# ESP32_VERSION_2.net
KiCad netlist of a schematic drawn in EAGLE
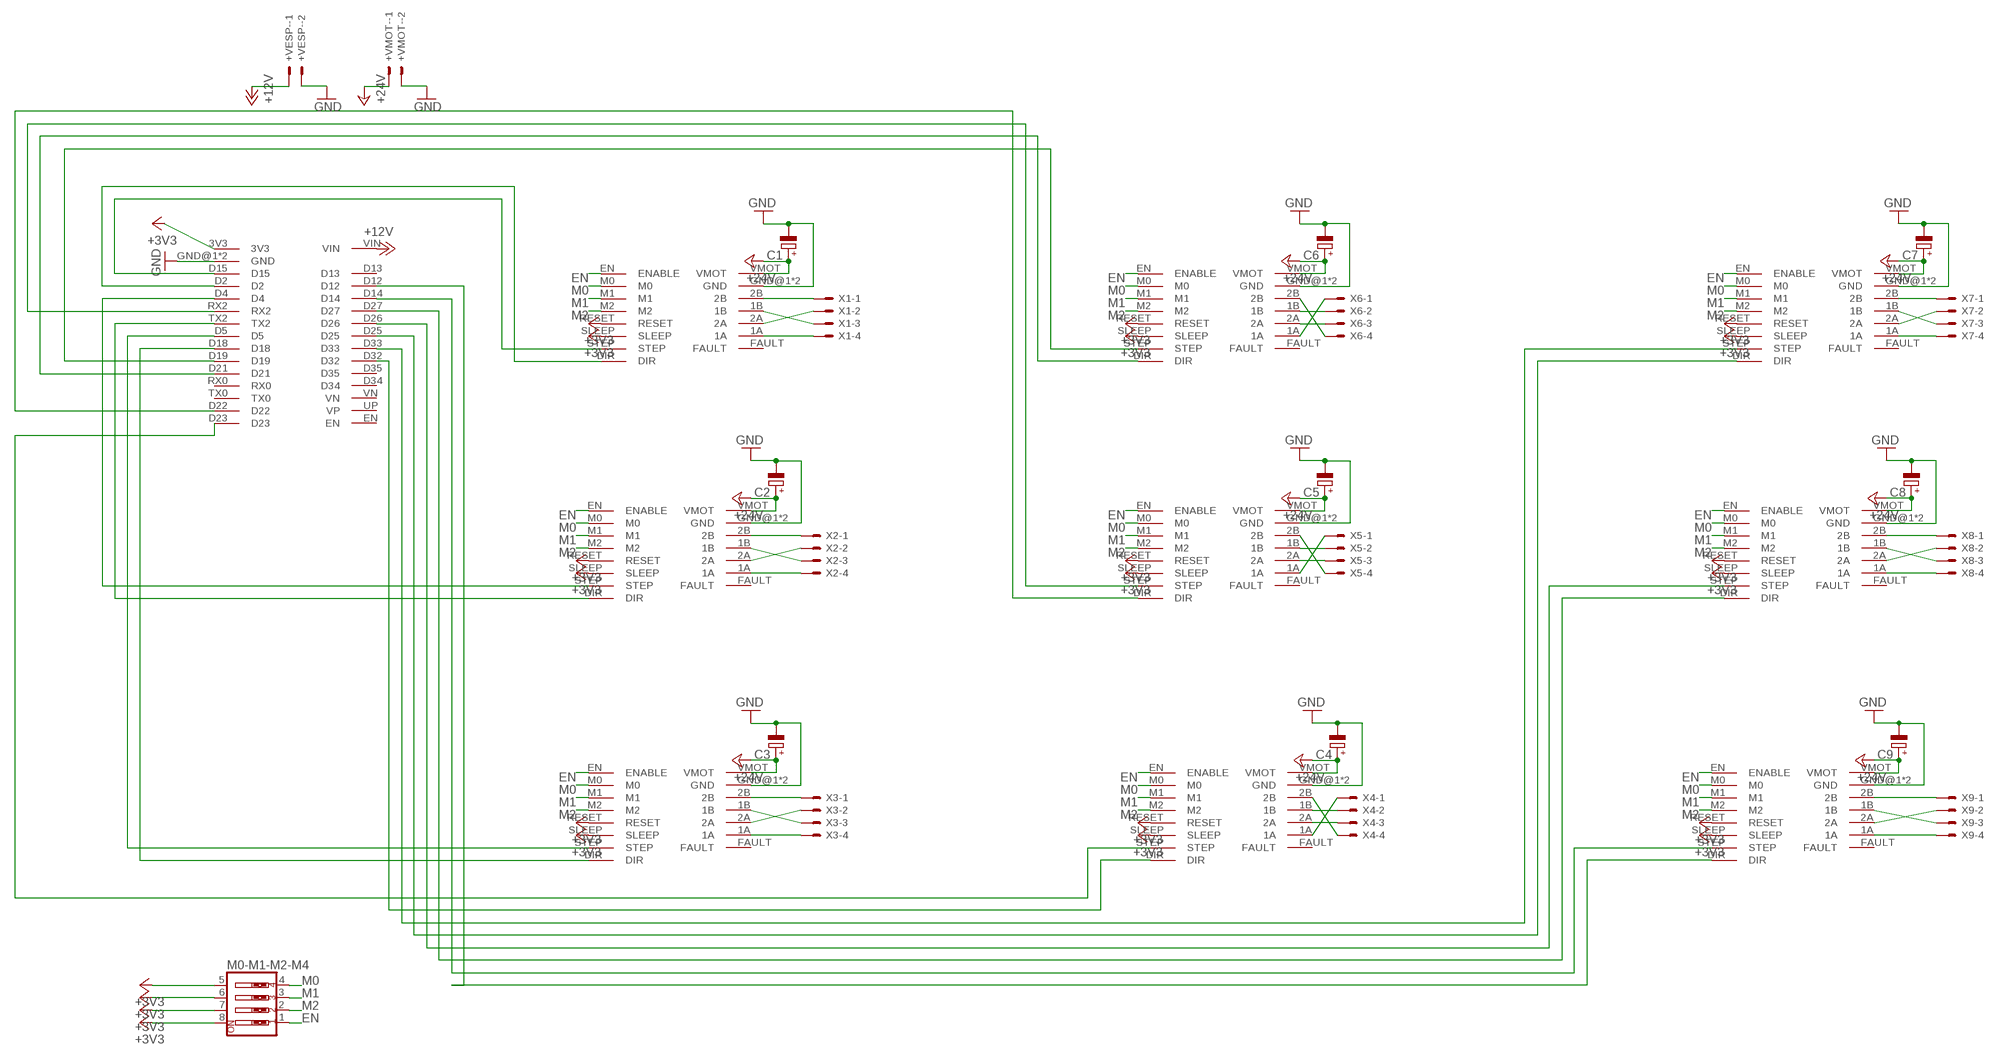
[diagram p0: schematic, sheet 1]

(export (version "E")
  (design (tool "Eeschema 10.0.6"))
  (components
    (comp (ref "+VESP-")
      (value "22-23-2021")
      (footprint "eagle-import:22-23-2021")
      (fields (field (name "MF") "MOLEX"))
      (libsource (lib "eagle-import") (part "22-23-2021"))
    )
    (comp (ref "+VMOT-")
      (value "22-23-2021")
      (footprint "eagle-import:22-23-2021")
      (fields (field (name "MF") "MOLEX"))
      (libsource (lib "eagle-import") (part "22-23-2021"))
    )
    (comp (ref "C1")
      (value "CPOL-EUE3.5-8")
      (footprint "eagle-import:E3,5-8")
      (libsource (lib "eagle-import") (part "CPOL-EUE3.5-8"))
    )
    (comp (ref "C2")
      (value "CPOL-EUE3.5-8")
      (footprint "eagle-import:E3,5-8")
      (libsource (lib "eagle-import") (part "CPOL-EUE3.5-8"))
    )
    (comp (ref "C3")
      (value "CPOL-EUE3.5-8")
      (footprint "eagle-import:E3,5-8")
      (libsource (lib "eagle-import") (part "CPOL-EUE3.5-8"))
    )
    (comp (ref "C4")
      (value "CPOL-EUE3.5-8")
      (footprint "eagle-import:E3,5-8")
      (libsource (lib "eagle-import") (part "CPOL-EUE3.5-8"))
    )
    (comp (ref "C5")
      (value "CPOL-EUE3.5-8")
      (footprint "eagle-import:E3,5-8")
      (libsource (lib "eagle-import") (part "CPOL-EUE3.5-8"))
    )
    (comp (ref "C6")
      (value "CPOL-EUE3.5-8")
      (footprint "eagle-import:E3,5-8")
      (libsource (lib "eagle-import") (part "CPOL-EUE3.5-8"))
    )
    (comp (ref "C7")
      (value "CPOL-EUE3.5-8")
      (footprint "eagle-import:E3,5-8")
      (libsource (lib "eagle-import") (part "CPOL-EUE3.5-8"))
    )
    (comp (ref "C8")
      (value "CPOL-EUE3.5-8")
      (footprint "eagle-import:E3,5-8")
      (libsource (lib "eagle-import") (part "CPOL-EUE3.5-8"))
    )
    (comp (ref "C9")
      (value "CPOL-EUE3.5-8")
      (footprint "eagle-import:E3,5-8")
      (libsource (lib "eagle-import") (part "CPOL-EUE3.5-8"))
    )
    (comp (ref "M0-M1-M2-M4")
      (value "SW_DIP-4")
      (footprint "eagle-import:EDG-04")
      (libsource (lib "eagle-import") (part "SW_DIP-4"))
    )
    (comp (ref "U$1")
      (value "DRV8825")
      (footprint "eagle-import:DRV8825")
      (libsource (lib "eagle-import") (part "DRV8825"))
    )
    (comp (ref "U$2")
      (value "DRV8825")
      (footprint "eagle-import:DRV8825")
      (libsource (lib "eagle-import") (part "DRV8825"))
    )
    (comp (ref "U$3")
      (value "STEPPER 0")
      (footprint "eagle-import:DRV8825")
      (libsource (lib "eagle-import") (part "DRV8825"))
    )
    (comp (ref "U$4")
      (value "DRV8825")
      (footprint "eagle-import:DRV8825")
      (libsource (lib "eagle-import") (part "DRV8825"))
    )
    (comp (ref "U$5")
      (value "DRV8825")
      (footprint "eagle-import:DRV8825")
      (libsource (lib "eagle-import") (part "DRV8825"))
    )
    (comp (ref "U$6")
      (value "DRV8825")
      (footprint "eagle-import:DRV8825")
      (libsource (lib "eagle-import") (part "DRV8825"))
    )
    (comp (ref "U$7")
      (value "DRV8825")
      (footprint "eagle-import:DRV8825")
      (libsource (lib "eagle-import") (part "DRV8825"))
    )
    (comp (ref "U$8")
      (value "DRV8825")
      (footprint "eagle-import:DRV8825")
      (libsource (lib "eagle-import") (part "DRV8825"))
    )
    (comp (ref "U$9")
      (value "DRV8825")
      (footprint "eagle-import:DRV8825")
      (libsource (lib "eagle-import") (part "DRV8825"))
    )
    (comp (ref "U$10")
      (value "ESP32")
      (footprint "eagle-import:ESP32")
      (libsource (lib "eagle-import") (part "ESP32"))
    )
    (comp (ref "X1")
      (value "22-23-2041")
      (footprint "eagle-import:22-23-2041")
      (fields (field (name "MF") "MOLEX"))
      (libsource (lib "eagle-import") (part "22-23-2041"))
    )
    (comp (ref "X2")
      (value "22-23-2041")
      (footprint "eagle-import:22-23-2041")
      (fields (field (name "MF") "MOLEX"))
      (libsource (lib "eagle-import") (part "22-23-2041"))
    )
    (comp (ref "X3")
      (value "22-23-2041")
      (footprint "eagle-import:22-23-2041")
      (fields (field (name "MF") "MOLEX"))
      (libsource (lib "eagle-import") (part "22-23-2041"))
    )
    (comp (ref "X4")
      (value "22-23-2041")
      (footprint "eagle-import:22-23-2041")
      (fields (field (name "MF") "MOLEX"))
      (libsource (lib "eagle-import") (part "22-23-2041"))
    )
    (comp (ref "X5")
      (value "22-23-2041")
      (footprint "eagle-import:22-23-2041")
      (fields (field (name "MF") "MOLEX"))
      (libsource (lib "eagle-import") (part "22-23-2041"))
    )
    (comp (ref "X6")
      (value "22-23-2041")
      (footprint "eagle-import:22-23-2041")
      (fields (field (name "MF") "MOLEX"))
      (libsource (lib "eagle-import") (part "22-23-2041"))
    )
    (comp (ref "X7")
      (value "22-23-2041")
      (footprint "eagle-import:22-23-2041")
      (fields (field (name "MF") "MOLEX"))
      (libsource (lib "eagle-import") (part "22-23-2041"))
    )
    (comp (ref "X8")
      (value "22-23-2041")
      (footprint "eagle-import:22-23-2041")
      (fields (field (name "MF") "MOLEX"))
      (libsource (lib "eagle-import") (part "22-23-2041"))
    )
    (comp (ref "X9")
      (value "22-23-2041")
      (footprint "eagle-import:22-23-2041")
      (fields (field (name "MF") "MOLEX"))
      (libsource (lib "eagle-import") (part "22-23-2041"))
    )
  )
  (nets
    (net (code "1") (name "+3V3") (class "Default")
      (node (ref "M0-M1-M2-M4") (pin "5") (pinfunction "5_5") (pintype "passive"))
      (node (ref "M0-M1-M2-M4") (pin "6") (pinfunction "6_6") (pintype "passive"))
      (node (ref "M0-M1-M2-M4") (pin "7") (pinfunction "7_7") (pintype "passive"))
      (node (ref "M0-M1-M2-M4") (pin "8") (pinfunction "8_8") (pintype "passive"))
      (node (ref "U$1") (pin "RESET") (pinfunction "RESET_RESET") (pintype "bidirectional"))
      (node (ref "U$1") (pin "SLEEP") (pinfunction "SLEEP_SLEEP") (pintype "bidirectional"))
      (node (ref "U$10") (pin "3V3") (pinfunction "3V3_3V3") (pintype "bidirectional"))
      (node (ref "U$2") (pin "RESET") (pinfunction "RESET_RESET") (pintype "bidirectional"))
      (node (ref "U$2") (pin "SLEEP") (pinfunction "SLEEP_SLEEP") (pintype "bidirectional"))
      (node (ref "U$3") (pin "RESET") (pinfunction "RESET_RESET") (pintype "bidirectional"))
      (node (ref "U$3") (pin "SLEEP") (pinfunction "SLEEP_SLEEP") (pintype "bidirectional"))
      (node (ref "U$4") (pin "RESET") (pinfunction "RESET_RESET") (pintype "bidirectional"))
      (node (ref "U$4") (pin "SLEEP") (pinfunction "SLEEP_SLEEP") (pintype "bidirectional"))
      (node (ref "U$5") (pin "RESET") (pinfunction "RESET_RESET") (pintype "bidirectional"))
      (node (ref "U$5") (pin "SLEEP") (pinfunction "SLEEP_SLEEP") (pintype "bidirectional"))
      (node (ref "U$6") (pin "RESET") (pinfunction "RESET_RESET") (pintype "bidirectional"))
      (node (ref "U$6") (pin "SLEEP") (pinfunction "SLEEP_SLEEP") (pintype "bidirectional"))
      (node (ref "U$7") (pin "RESET") (pinfunction "RESET_RESET") (pintype "bidirectional"))
      (node (ref "U$7") (pin "SLEEP") (pinfunction "SLEEP_SLEEP") (pintype "bidirectional"))
      (node (ref "U$8") (pin "RESET") (pinfunction "RESET_RESET") (pintype "bidirectional"))
      (node (ref "U$8") (pin "SLEEP") (pinfunction "SLEEP_SLEEP") (pintype "bidirectional"))
      (node (ref "U$9") (pin "RESET") (pinfunction "RESET_RESET") (pintype "bidirectional"))
      (node (ref "U$9") (pin "SLEEP") (pinfunction "SLEEP_SLEEP") (pintype "bidirectional"))
    )
    (net (code "2") (name "+12V") (class "Default")
      (node (ref "+VESP-") (pin "1") (pinfunction "S_1") (pintype "passive"))
      (node (ref "U$10") (pin "VIN") (pinfunction "VIN_VIN") (pintype "bidirectional"))
    )
    (net (code "3") (name "+24V") (class "Default")
      (node (ref "+VMOT-") (pin "1") (pinfunction "S_1") (pintype "passive"))
      (node (ref "C1") (pin "+") (pinfunction "+_+") (pintype "passive"))
      (node (ref "C2") (pin "+") (pinfunction "+_+") (pintype "passive"))
      (node (ref "C3") (pin "+") (pinfunction "+_+") (pintype "passive"))
      (node (ref "C4") (pin "+") (pinfunction "+_+") (pintype "passive"))
      (node (ref "C5") (pin "+") (pinfunction "+_+") (pintype "passive"))
      (node (ref "C6") (pin "+") (pinfunction "+_+") (pintype "passive"))
      (node (ref "C7") (pin "+") (pinfunction "+_+") (pintype "passive"))
      (node (ref "C8") (pin "+") (pinfunction "+_+") (pintype "passive"))
      (node (ref "C9") (pin "+") (pinfunction "+_+") (pintype "passive"))
      (node (ref "U$1") (pin "VMOT") (pinfunction "VMOT_VMOT") (pintype "bidirectional"))
      (node (ref "U$2") (pin "VMOT") (pinfunction "VMOT_VMOT") (pintype "bidirectional"))
      (node (ref "U$3") (pin "VMOT") (pinfunction "VMOT_VMOT") (pintype "bidirectional"))
      (node (ref "U$4") (pin "VMOT") (pinfunction "VMOT_VMOT") (pintype "bidirectional"))
      (node (ref "U$5") (pin "VMOT") (pinfunction "VMOT_VMOT") (pintype "bidirectional"))
      (node (ref "U$6") (pin "VMOT") (pinfunction "VMOT_VMOT") (pintype "bidirectional"))
      (node (ref "U$7") (pin "VMOT") (pinfunction "VMOT_VMOT") (pintype "bidirectional"))
      (node (ref "U$8") (pin "VMOT") (pinfunction "VMOT_VMOT") (pintype "bidirectional"))
      (node (ref "U$9") (pin "VMOT") (pinfunction "VMOT_VMOT") (pintype "bidirectional"))
    )
    (net (code "4") (name "/EN") (class "Default")
      (node (ref "M0-M1-M2-M4") (pin "1") (pinfunction "1_1") (pintype "passive"))
      (node (ref "U$1") (pin "EN") (pinfunction "ENABLE_EN") (pintype "bidirectional"))
      (node (ref "U$2") (pin "EN") (pinfunction "ENABLE_EN") (pintype "bidirectional"))
      (node (ref "U$3") (pin "EN") (pinfunction "ENABLE_EN") (pintype "bidirectional"))
      (node (ref "U$4") (pin "EN") (pinfunction "ENABLE_EN") (pintype "bidirectional"))
      (node (ref "U$5") (pin "EN") (pinfunction "ENABLE_EN") (pintype "bidirectional"))
      (node (ref "U$6") (pin "EN") (pinfunction "ENABLE_EN") (pintype "bidirectional"))
      (node (ref "U$7") (pin "EN") (pinfunction "ENABLE_EN") (pintype "bidirectional"))
      (node (ref "U$8") (pin "EN") (pinfunction "ENABLE_EN") (pintype "bidirectional"))
      (node (ref "U$9") (pin "EN") (pinfunction "ENABLE_EN") (pintype "bidirectional"))
    )
    (net (code "5") (name "/M0") (class "Default")
      (node (ref "M0-M1-M2-M4") (pin "4") (pinfunction "4_4") (pintype "passive"))
      (node (ref "U$1") (pin "M0") (pinfunction "M0_M0") (pintype "bidirectional"))
      (node (ref "U$2") (pin "M0") (pinfunction "M0_M0") (pintype "bidirectional"))
      (node (ref "U$3") (pin "M0") (pinfunction "M0_M0") (pintype "bidirectional"))
      (node (ref "U$4") (pin "M0") (pinfunction "M0_M0") (pintype "bidirectional"))
      (node (ref "U$5") (pin "M0") (pinfunction "M0_M0") (pintype "bidirectional"))
      (node (ref "U$6") (pin "M0") (pinfunction "M0_M0") (pintype "bidirectional"))
      (node (ref "U$7") (pin "M0") (pinfunction "M0_M0") (pintype "bidirectional"))
      (node (ref "U$8") (pin "M0") (pinfunction "M0_M0") (pintype "bidirectional"))
      (node (ref "U$9") (pin "M0") (pinfunction "M0_M0") (pintype "bidirectional"))
    )
    (net (code "6") (name "/M1") (class "Default")
      (node (ref "M0-M1-M2-M4") (pin "3") (pinfunction "3_3") (pintype "passive"))
      (node (ref "U$1") (pin "M1") (pinfunction "M1_M1") (pintype "bidirectional"))
      (node (ref "U$2") (pin "M1") (pinfunction "M1_M1") (pintype "bidirectional"))
      (node (ref "U$3") (pin "M1") (pinfunction "M1_M1") (pintype "bidirectional"))
      (node (ref "U$4") (pin "M1") (pinfunction "M1_M1") (pintype "bidirectional"))
      (node (ref "U$5") (pin "M1") (pinfunction "M1_M1") (pintype "bidirectional"))
      (node (ref "U$6") (pin "M1") (pinfunction "M1_M1") (pintype "bidirectional"))
      (node (ref "U$7") (pin "M1") (pinfunction "M1_M1") (pintype "bidirectional"))
      (node (ref "U$8") (pin "M1") (pinfunction "M1_M1") (pintype "bidirectional"))
      (node (ref "U$9") (pin "M1") (pinfunction "M1_M1") (pintype "bidirectional"))
    )
    (net (code "7") (name "/M2") (class "Default")
      (node (ref "M0-M1-M2-M4") (pin "2") (pinfunction "2_2") (pintype "passive"))
      (node (ref "U$1") (pin "M2") (pinfunction "M2_M2") (pintype "bidirectional"))
      (node (ref "U$2") (pin "M2") (pinfunction "M2_M2") (pintype "bidirectional"))
      (node (ref "U$3") (pin "M2") (pinfunction "M2_M2") (pintype "bidirectional"))
      (node (ref "U$4") (pin "M2") (pinfunction "M2_M2") (pintype "bidirectional"))
      (node (ref "U$5") (pin "M2") (pinfunction "M2_M2") (pintype "bidirectional"))
      (node (ref "U$6") (pin "M2") (pinfunction "M2_M2") (pintype "bidirectional"))
      (node (ref "U$7") (pin "M2") (pinfunction "M2_M2") (pintype "bidirectional"))
      (node (ref "U$8") (pin "M2") (pinfunction "M2_M2") (pintype "bidirectional"))
      (node (ref "U$9") (pin "M2") (pinfunction "M2_M2") (pintype "bidirectional"))
    )
    (net (code "8") (name "GND") (class "Default")
      (node (ref "+VESP-") (pin "2") (pinfunction "S_2") (pintype "passive"))
      (node (ref "+VMOT-") (pin "2") (pinfunction "S_2") (pintype "passive"))
      (node (ref "C1") (pin "-") (pinfunction "-_-") (pintype "passive"))
      (node (ref "C2") (pin "-") (pinfunction "-_-") (pintype "passive"))
      (node (ref "C3") (pin "-") (pinfunction "-_-") (pintype "passive"))
      (node (ref "C4") (pin "-") (pinfunction "-_-") (pintype "passive"))
      (node (ref "C5") (pin "-") (pinfunction "-_-") (pintype "passive"))
      (node (ref "C6") (pin "-") (pinfunction "-_-") (pintype "passive"))
      (node (ref "C7") (pin "-") (pinfunction "-_-") (pintype "passive"))
      (node (ref "C8") (pin "-") (pinfunction "-_-") (pintype "passive"))
      (node (ref "C9") (pin "-") (pinfunction "-_-") (pintype "passive"))
      (node (ref "U$1") (pin "GND@1") (pinfunction "GND_GND@1") (pintype "bidirectional"))
      (node (ref "U$1") (pin "GND@2") (pinfunction "GND_GND@2") (pintype "bidirectional"))
      (node (ref "U$10") (pin "GND@1") (pinfunction "GND_GND@1") (pintype "bidirectional"))
      (node (ref "U$10") (pin "GND@2") (pinfunction "GND_GND@2") (pintype "bidirectional"))
      (node (ref "U$2") (pin "GND@1") (pinfunction "GND_GND@1") (pintype "bidirectional"))
      (node (ref "U$2") (pin "GND@2") (pinfunction "GND_GND@2") (pintype "bidirectional"))
      (node (ref "U$3") (pin "GND@1") (pinfunction "GND_GND@1") (pintype "bidirectional"))
      (node (ref "U$3") (pin "GND@2") (pinfunction "GND_GND@2") (pintype "bidirectional"))
      (node (ref "U$4") (pin "GND@1") (pinfunction "GND_GND@1") (pintype "bidirectional"))
      (node (ref "U$4") (pin "GND@2") (pinfunction "GND_GND@2") (pintype "bidirectional"))
      (node (ref "U$5") (pin "GND@1") (pinfunction "GND_GND@1") (pintype "bidirectional"))
      (node (ref "U$5") (pin "GND@2") (pinfunction "GND_GND@2") (pintype "bidirectional"))
      (node (ref "U$6") (pin "GND@1") (pinfunction "GND_GND@1") (pintype "bidirectional"))
      (node (ref "U$6") (pin "GND@2") (pinfunction "GND_GND@2") (pintype "bidirectional"))
      (node (ref "U$7") (pin "GND@1") (pinfunction "GND_GND@1") (pintype "bidirectional"))
      (node (ref "U$7") (pin "GND@2") (pinfunction "GND_GND@2") (pintype "bidirectional"))
      (node (ref "U$8") (pin "GND@1") (pinfunction "GND_GND@1") (pintype "bidirectional"))
      (node (ref "U$8") (pin "GND@2") (pinfunction "GND_GND@2") (pintype "bidirectional"))
      (node (ref "U$9") (pin "GND@1") (pinfunction "GND_GND@1") (pintype "bidirectional"))
      (node (ref "U$9") (pin "GND@2") (pinfunction "GND_GND@2") (pintype "bidirectional"))
    )
    (net (code "9") (name "Net-(U$1-PadDIR)") (class "Default")
      (node (ref "U$1") (pin "DIR") (pinfunction "DIR_DIR") (pintype "bidirectional"))
      (node (ref "U$10") (pin "D18") (pinfunction "D18_D18") (pintype "bidirectional"))
    )
    (net (code "10") (name "Net-(U$1-PadSTEP)") (class "Default")
      (node (ref "U$1") (pin "STEP") (pinfunction "STEP_STEP") (pintype "bidirectional"))
      (node (ref "U$10") (pin "D5") (pinfunction "D5_D5") (pintype "bidirectional"))
    )
    (net (code "11") (name "Net-(U$10-PadD2)") (class "Default")
      (node (ref "U$10") (pin "D2") (pinfunction "D2_D2") (pintype "bidirectional"))
      (node (ref "U$3") (pin "DIR") (pinfunction "DIR_DIR") (pintype "bidirectional"))
    )
    (net (code "12") (name "Net-(U$10-PadD4)") (class "Default")
      (node (ref "U$10") (pin "D4") (pinfunction "D4_D4") (pintype "bidirectional"))
      (node (ref "U$2") (pin "STEP") (pinfunction "STEP_STEP") (pintype "bidirectional"))
    )
    (net (code "13") (name "Net-(U$10-PadD12)") (class "Default")
      (node (ref "U$10") (pin "D12") (pinfunction "D12_D12") (pintype "bidirectional"))
      (node (ref "U$9") (pin "DIR") (pinfunction "DIR_DIR") (pintype "bidirectional"))
    )
    (net (code "14") (name "Net-(U$10-PadD14)") (class "Default")
      (node (ref "U$10") (pin "D14") (pinfunction "D14_D14") (pintype "bidirectional"))
      (node (ref "U$9") (pin "STEP") (pinfunction "STEP_STEP") (pintype "bidirectional"))
    )
    (net (code "15") (name "Net-(U$10-PadD15)") (class "Default")
      (node (ref "U$10") (pin "D15") (pinfunction "D15_D15") (pintype "bidirectional"))
      (node (ref "U$3") (pin "STEP") (pinfunction "STEP_STEP") (pintype "bidirectional"))
    )
    (net (code "16") (name "Net-(U$10-PadD19)") (class "Default")
      (node (ref "U$10") (pin "D19") (pinfunction "D19_D19") (pintype "bidirectional"))
      (node (ref "U$4") (pin "STEP") (pinfunction "STEP_STEP") (pintype "bidirectional"))
    )
    (net (code "17") (name "Net-(U$10-PadD21)") (class "Default")
      (node (ref "U$10") (pin "D21") (pinfunction "D21_D21") (pintype "bidirectional"))
      (node (ref "U$4") (pin "DIR") (pinfunction "DIR_DIR") (pintype "bidirectional"))
    )
    (net (code "18") (name "Net-(U$10-PadD22)") (class "Default")
      (node (ref "U$10") (pin "D22") (pinfunction "D22_D22") (pintype "bidirectional"))
      (node (ref "U$5") (pin "DIR") (pinfunction "DIR_DIR") (pintype "bidirectional"))
    )
    (net (code "19") (name "Net-(U$10-PadD23)") (class "Default")
      (node (ref "U$10") (pin "D23") (pinfunction "D23_D23") (pintype "bidirectional"))
      (node (ref "U$6") (pin "STEP") (pinfunction "STEP_STEP") (pintype "bidirectional"))
    )
    (net (code "20") (name "Net-(U$10-PadD25)") (class "Default")
      (node (ref "U$10") (pin "D25") (pinfunction "D25_D25") (pintype "bidirectional"))
      (node (ref "U$7") (pin "DIR") (pinfunction "DIR_DIR") (pintype "bidirectional"))
    )
    (net (code "21") (name "Net-(U$10-PadD26)") (class "Default")
      (node (ref "U$10") (pin "D26") (pinfunction "D26_D26") (pintype "bidirectional"))
      (node (ref "U$8") (pin "STEP") (pinfunction "STEP_STEP") (pintype "bidirectional"))
    )
    (net (code "22") (name "Net-(U$10-PadD27)") (class "Default")
      (node (ref "U$10") (pin "D27") (pinfunction "D27_D27") (pintype "bidirectional"))
      (node (ref "U$8") (pin "DIR") (pinfunction "DIR_DIR") (pintype "bidirectional"))
    )
    (net (code "23") (name "Net-(U$10-PadD32)") (class "Default")
      (node (ref "U$10") (pin "D32") (pinfunction "D32_D32") (pintype "bidirectional"))
      (node (ref "U$6") (pin "DIR") (pinfunction "DIR_DIR") (pintype "bidirectional"))
    )
    (net (code "24") (name "Net-(U$10-PadD33)") (class "Default")
      (node (ref "U$10") (pin "D33") (pinfunction "D33_D33") (pintype "bidirectional"))
      (node (ref "U$7") (pin "STEP") (pinfunction "STEP_STEP") (pintype "bidirectional"))
    )
    (net (code "25") (name "Net-(U$10-PadRX2)") (class "Default")
      (node (ref "U$10") (pin "RX2") (pinfunction "RX2_RX2") (pintype "bidirectional"))
      (node (ref "U$5") (pin "STEP") (pinfunction "STEP_STEP") (pintype "bidirectional"))
    )
    (net (code "26") (name "Net-(U$10-PadTX2)") (class "Default")
      (node (ref "U$10") (pin "TX2") (pinfunction "TX2_TX2") (pintype "bidirectional"))
      (node (ref "U$2") (pin "DIR") (pinfunction "DIR_DIR") (pintype "bidirectional"))
    )
    (net (code "27") (name "Net-(X1A-S)") (class "Default")
      (node (ref "U$3") (pin "2B") (pinfunction "2B_2B") (pintype "bidirectional"))
      (node (ref "X1") (pin "1") (pinfunction "S_1") (pintype "passive"))
    )
    (net (code "28") (name "Net-(X1B-S)") (class "Default")
      (node (ref "U$3") (pin "2A") (pinfunction "2A_2A") (pintype "bidirectional"))
      (node (ref "X1") (pin "2") (pinfunction "S_2") (pintype "passive"))
    )
    (net (code "29") (name "Net-(X1C-S)") (class "Default")
      (node (ref "U$3") (pin "1B") (pinfunction "1B_1B") (pintype "bidirectional"))
      (node (ref "X1") (pin "3") (pinfunction "S_3") (pintype "passive"))
    )
    (net (code "30") (name "Net-(X1D-S)") (class "Default")
      (node (ref "U$3") (pin "1A") (pinfunction "1A_1A") (pintype "bidirectional"))
      (node (ref "X1") (pin "4") (pinfunction "S_4") (pintype "passive"))
    )
    (net (code "31") (name "Net-(X2A-S)") (class "Default")
      (node (ref "U$2") (pin "2B") (pinfunction "2B_2B") (pintype "bidirectional"))
      (node (ref "X2") (pin "1") (pinfunction "S_1") (pintype "passive"))
    )
    (net (code "32") (name "Net-(X2B-S)") (class "Default")
      (node (ref "U$2") (pin "2A") (pinfunction "2A_2A") (pintype "bidirectional"))
      (node (ref "X2") (pin "2") (pinfunction "S_2") (pintype "passive"))
    )
    (net (code "33") (name "Net-(X2C-S)") (class "Default")
      (node (ref "U$2") (pin "1B") (pinfunction "1B_1B") (pintype "bidirectional"))
      (node (ref "X2") (pin "3") (pinfunction "S_3") (pintype "passive"))
    )
    (net (code "34") (name "Net-(X2D-S)") (class "Default")
      (node (ref "U$2") (pin "1A") (pinfunction "1A_1A") (pintype "bidirectional"))
      (node (ref "X2") (pin "4") (pinfunction "S_4") (pintype "passive"))
    )
    (net (code "35") (name "Net-(X3A-S)") (class "Default")
      (node (ref "U$1") (pin "2B") (pinfunction "2B_2B") (pintype "bidirectional"))
      (node (ref "X3") (pin "1") (pinfunction "S_1") (pintype "passive"))
    )
    (net (code "36") (name "Net-(X3B-S)") (class "Default")
      (node (ref "U$1") (pin "2A") (pinfunction "2A_2A") (pintype "bidirectional"))
      (node (ref "X3") (pin "2") (pinfunction "S_2") (pintype "passive"))
    )
    (net (code "37") (name "Net-(X3C-S)") (class "Default")
      (node (ref "U$1") (pin "1B") (pinfunction "1B_1B") (pintype "bidirectional"))
      (node (ref "X3") (pin "3") (pinfunction "S_3") (pintype "passive"))
    )
    (net (code "38") (name "Net-(X3D-S)") (class "Default")
      (node (ref "U$1") (pin "1A") (pinfunction "1A_1A") (pintype "bidirectional"))
      (node (ref "X3") (pin "4") (pinfunction "S_4") (pintype "passive"))
    )
    (net (code "39") (name "Net-(X4A-S)") (class "Default")
      (node (ref "U$6") (pin "1A") (pinfunction "1A_1A") (pintype "bidirectional"))
      (node (ref "X4") (pin "1") (pinfunction "S_1") (pintype "passive"))
    )
    (net (code "40") (name "Net-(X4B-S)") (class "Default")
      (node (ref "U$6") (pin "1B") (pinfunction "1B_1B") (pintype "bidirectional"))
      (node (ref "X4") (pin "2") (pinfunction "S_2") (pintype "passive"))
    )
    (net (code "41") (name "Net-(X4C-S)") (class "Default")
      (node (ref "U$6") (pin "2A") (pinfunction "2A_2A") (pintype "bidirectional"))
      (node (ref "X4") (pin "3") (pinfunction "S_3") (pintype "passive"))
    )
    (net (code "42") (name "Net-(X4D-S)") (class "Default")
      (node (ref "U$6") (pin "2B") (pinfunction "2B_2B") (pintype "bidirectional"))
      (node (ref "X4") (pin "4") (pinfunction "S_4") (pintype "passive"))
    )
    (net (code "43") (name "Net-(X5A-S)") (class "Default")
      (node (ref "U$5") (pin "1A") (pinfunction "1A_1A") (pintype "bidirectional"))
      (node (ref "X5") (pin "1") (pinfunction "S_1") (pintype "passive"))
    )
    (net (code "44") (name "Net-(X5B-S)") (class "Default")
      (node (ref "U$5") (pin "1B") (pinfunction "1B_1B") (pintype "bidirectional"))
      (node (ref "X5") (pin "2") (pinfunction "S_2") (pintype "passive"))
    )
    (net (code "45") (name "Net-(X5C-S)") (class "Default")
      (node (ref "U$5") (pin "2A") (pinfunction "2A_2A") (pintype "bidirectional"))
      (node (ref "X5") (pin "3") (pinfunction "S_3") (pintype "passive"))
    )
    (net (code "46") (name "Net-(X5D-S)") (class "Default")
      (node (ref "U$5") (pin "2B") (pinfunction "2B_2B") (pintype "bidirectional"))
      (node (ref "X5") (pin "4") (pinfunction "S_4") (pintype "passive"))
    )
    (net (code "47") (name "Net-(X6A-S)") (class "Default")
      (node (ref "U$4") (pin "1A") (pinfunction "1A_1A") (pintype "bidirectional"))
      (node (ref "X6") (pin "1") (pinfunction "S_1") (pintype "passive"))
    )
    (net (code "48") (name "Net-(X6B-S)") (class "Default")
      (node (ref "U$4") (pin "1B") (pinfunction "1B_1B") (pintype "bidirectional"))
      (node (ref "X6") (pin "2") (pinfunction "S_2") (pintype "passive"))
    )
    (net (code "49") (name "Net-(X6C-S)") (class "Default")
      (node (ref "U$4") (pin "2A") (pinfunction "2A_2A") (pintype "bidirectional"))
      (node (ref "X6") (pin "3") (pinfunction "S_3") (pintype "passive"))
    )
    (net (code "50") (name "Net-(X6D-S)") (class "Default")
      (node (ref "U$4") (pin "2B") (pinfunction "2B_2B") (pintype "bidirectional"))
      (node (ref "X6") (pin "4") (pinfunction "S_4") (pintype "passive"))
    )
    (net (code "51") (name "Net-(X7A-S)") (class "Default")
      (node (ref "U$7") (pin "2B") (pinfunction "2B_2B") (pintype "bidirectional"))
      (node (ref "X7") (pin "1") (pinfunction "S_1") (pintype "passive"))
    )
    (net (code "52") (name "Net-(X7B-S)") (class "Default")
      (node (ref "U$7") (pin "2A") (pinfunction "2A_2A") (pintype "bidirectional"))
      (node (ref "X7") (pin "2") (pinfunction "S_2") (pintype "passive"))
    )
    (net (code "53") (name "Net-(X7C-S)") (class "Default")
      (node (ref "U$7") (pin "1B") (pinfunction "1B_1B") (pintype "bidirectional"))
      (node (ref "X7") (pin "3") (pinfunction "S_3") (pintype "passive"))
    )
    (net (code "54") (name "Net-(X7D-S)") (class "Default")
      (node (ref "U$7") (pin "1A") (pinfunction "1A_1A") (pintype "bidirectional"))
      (node (ref "X7") (pin "4") (pinfunction "S_4") (pintype "passive"))
    )
    (net (code "55") (name "Net-(X8A-S)") (class "Default")
      (node (ref "U$8") (pin "2B") (pinfunction "2B_2B") (pintype "bidirectional"))
      (node (ref "X8") (pin "1") (pinfunction "S_1") (pintype "passive"))
    )
    (net (code "56") (name "Net-(X8B-S)") (class "Default")
      (node (ref "U$8") (pin "2A") (pinfunction "2A_2A") (pintype "bidirectional"))
      (node (ref "X8") (pin "2") (pinfunction "S_2") (pintype "passive"))
    )
    (net (code "57") (name "Net-(X8C-S)") (class "Default")
      (node (ref "U$8") (pin "1B") (pinfunction "1B_1B") (pintype "bidirectional"))
      (node (ref "X8") (pin "3") (pinfunction "S_3") (pintype "passive"))
    )
    (net (code "58") (name "Net-(X8D-S)") (class "Default")
      (node (ref "U$8") (pin "1A") (pinfunction "1A_1A") (pintype "bidirectional"))
      (node (ref "X8") (pin "4") (pinfunction "S_4") (pintype "passive"))
    )
    (net (code "59") (name "Net-(X9A-S)") (class "Default")
      (node (ref "U$9") (pin "2B") (pinfunction "2B_2B") (pintype "bidirectional"))
      (node (ref "X9") (pin "1") (pinfunction "S_1") (pintype "passive"))
    )
    (net (code "60") (name "Net-(X9B-S)") (class "Default")
      (node (ref "U$9") (pin "2A") (pinfunction "2A_2A") (pintype "bidirectional"))
      (node (ref "X9") (pin "2") (pinfunction "S_2") (pintype "passive"))
    )
    (net (code "61") (name "Net-(X9C-S)") (class "Default")
      (node (ref "U$9") (pin "1B") (pinfunction "1B_1B") (pintype "bidirectional"))
      (node (ref "X9") (pin "3") (pinfunction "S_3") (pintype "passive"))
    )
    (net (code "62") (name "Net-(X9D-S)") (class "Default")
      (node (ref "U$9") (pin "1A") (pinfunction "1A_1A") (pintype "bidirectional"))
      (node (ref "X9") (pin "4") (pinfunction "S_4") (pintype "passive"))
    )
    (net (code "63") (name "unconnected-(U$1-PadFAULT)") (class "Default")
      (node (ref "U$1") (pin "FAULT") (pinfunction "FAULT_FAULT") (pintype "bidirectional"))
    )
    (net (code "64") (name "unconnected-(U$2-PadFAULT)") (class "Default")
      (node (ref "U$2") (pin "FAULT") (pinfunction "FAULT_FAULT") (pintype "bidirectional"))
    )
    (net (code "65") (name "unconnected-(U$3-PadFAULT)") (class "Default")
      (node (ref "U$3") (pin "FAULT") (pinfunction "FAULT_FAULT") (pintype "bidirectional"))
    )
    (net (code "66") (name "unconnected-(U$4-PadFAULT)") (class "Default")
      (node (ref "U$4") (pin "FAULT") (pinfunction "FAULT_FAULT") (pintype "bidirectional"))
    )
    (net (code "67") (name "unconnected-(U$5-PadFAULT)") (class "Default")
      (node (ref "U$5") (pin "FAULT") (pinfunction "FAULT_FAULT") (pintype "bidirectional"))
    )
    (net (code "68") (name "unconnected-(U$6-PadFAULT)") (class "Default")
      (node (ref "U$6") (pin "FAULT") (pinfunction "FAULT_FAULT") (pintype "bidirectional"))
    )
    (net (code "69") (name "unconnected-(U$7-PadFAULT)") (class "Default")
      (node (ref "U$7") (pin "FAULT") (pinfunction "FAULT_FAULT") (pintype "bidirectional"))
    )
    (net (code "70") (name "unconnected-(U$8-PadFAULT)") (class "Default")
      (node (ref "U$8") (pin "FAULT") (pinfunction "FAULT_FAULT") (pintype "bidirectional"))
    )
    (net (code "71") (name "unconnected-(U$9-PadFAULT)") (class "Default")
      (node (ref "U$9") (pin "FAULT") (pinfunction "FAULT_FAULT") (pintype "bidirectional"))
    )
    (net (code "72") (name "unconnected-(U$10-PadD13)") (class "Default")
      (node (ref "U$10") (pin "D13") (pinfunction "D13_D13") (pintype "bidirectional"))
    )
    (net (code "73") (name "unconnected-(U$10-PadD34)") (class "Default")
      (node (ref "U$10") (pin "D34") (pinfunction "D34_D34") (pintype "bidirectional"))
    )
    (net (code "74") (name "unconnected-(U$10-PadD35)") (class "Default")
      (node (ref "U$10") (pin "D35") (pinfunction "D35_D35") (pintype "bidirectional"))
    )
    (net (code "75") (name "unconnected-(U$10-PadEN)") (class "Default")
      (node (ref "U$10") (pin "EN") (pinfunction "EN_EN") (pintype "bidirectional"))
    )
    (net (code "76") (name "unconnected-(U$10-PadRX0)") (class "Default")
      (node (ref "U$10") (pin "RX0") (pinfunction "RX0_RX0") (pintype "bidirectional"))
    )
    (net (code "77") (name "unconnected-(U$10-PadTX0)") (class "Default")
      (node (ref "U$10") (pin "TX0") (pinfunction "TX0_TX0") (pintype "bidirectional"))
    )
    (net (code "78") (name "unconnected-(U$10-PadVN)") (class "Default")
      (node (ref "U$10") (pin "VN") (pinfunction "VN_VN") (pintype "bidirectional"))
    )
    (net (code "79") (name "unconnected-(U$10-VP-PadUP)") (class "Default")
      (node (ref "U$10") (pin "UP") (pinfunction "VP_UP") (pintype "bidirectional"))
    )
  )
)
